# cerebro5_8_doubleboost_singlebattery.net
KiCad netlist of a schematic drawn in EAGLE
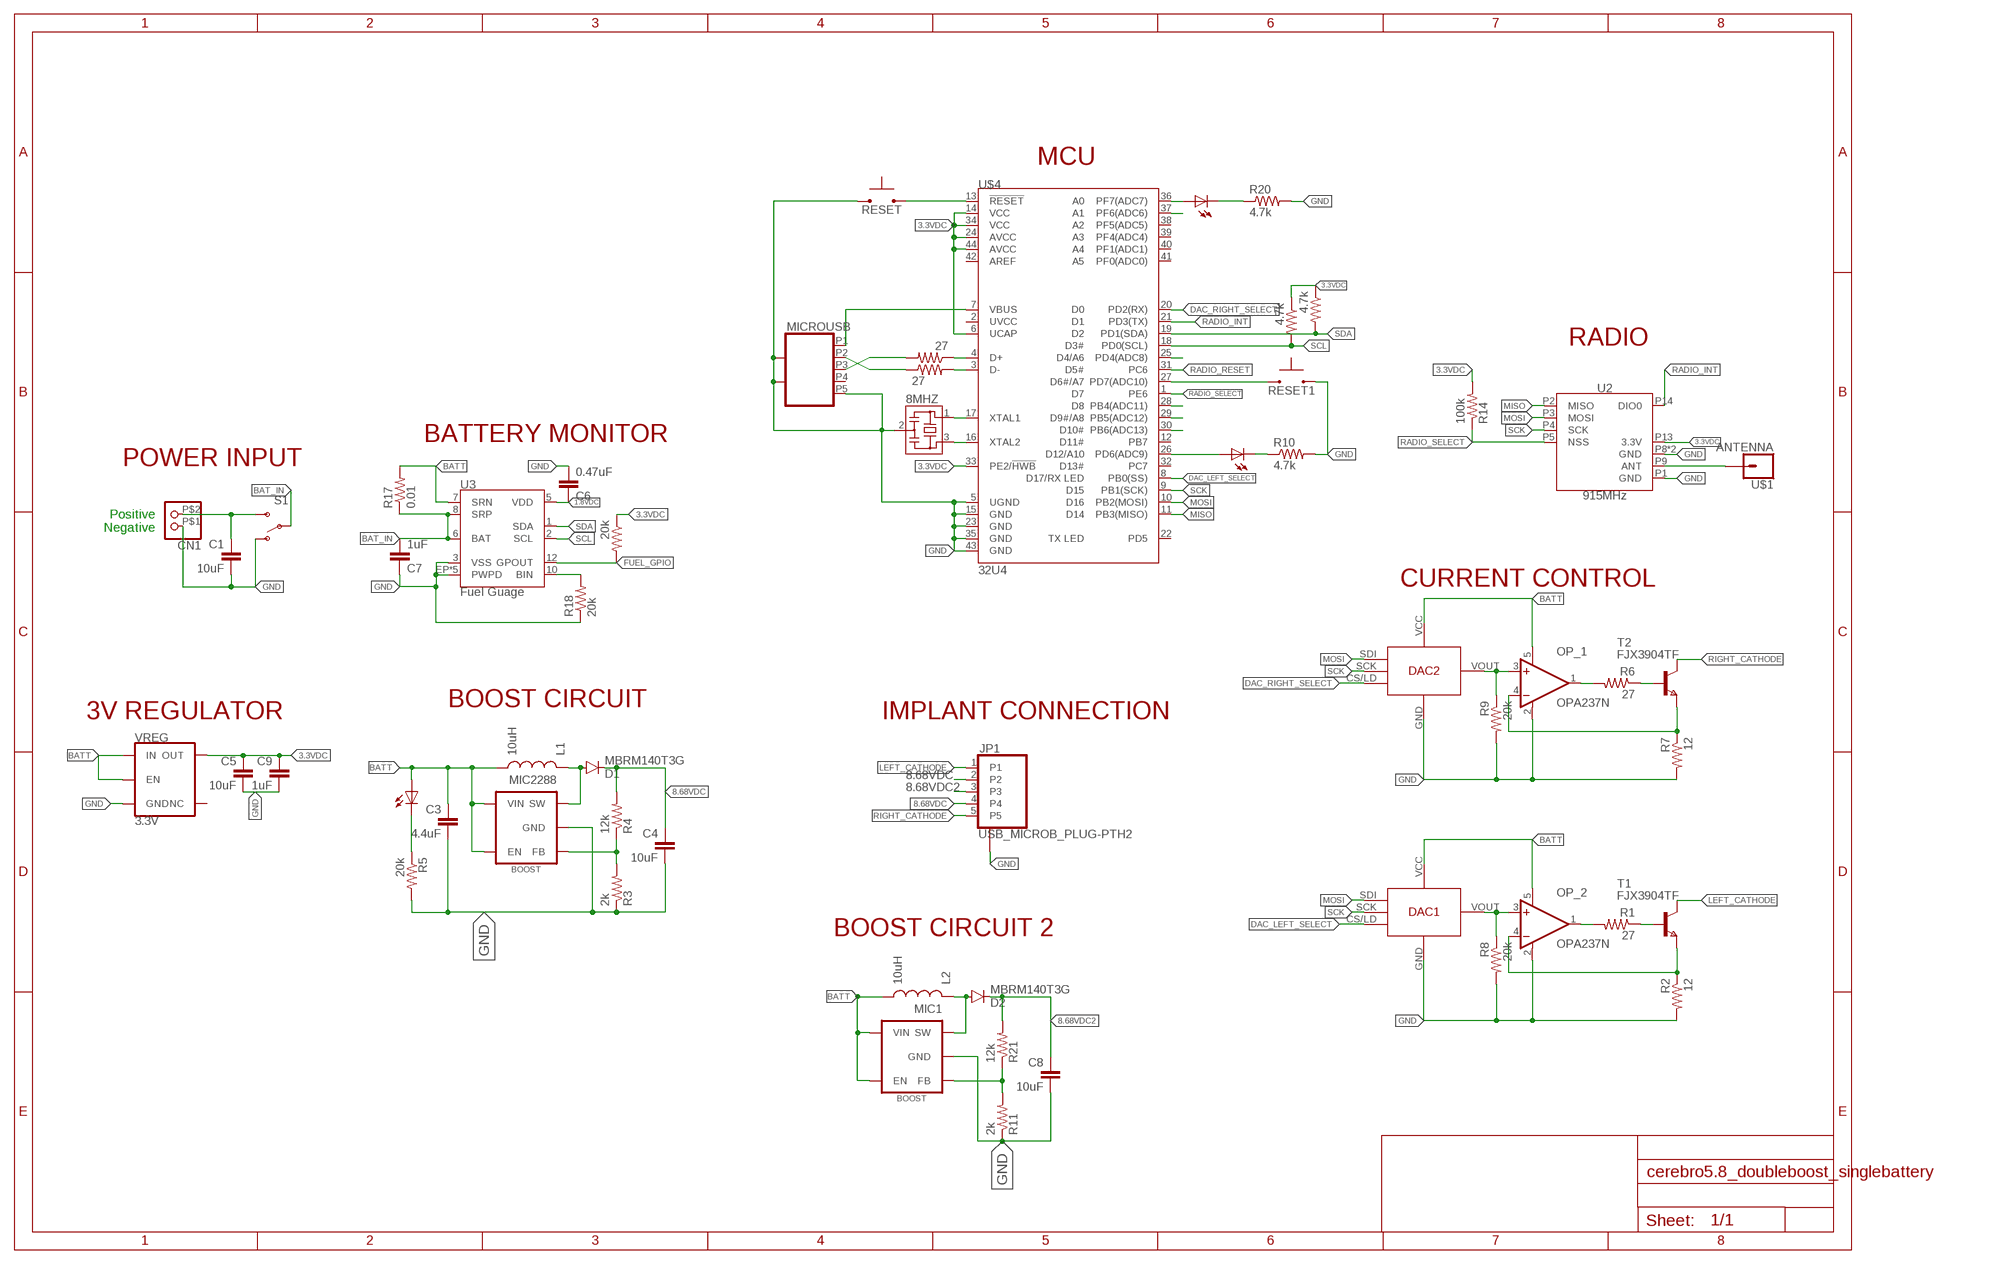
[diagram p0: schematic, sheet 1]

(export (version "E")
  (design (tool "Eeschema 10.0.6"))
  (components
    (comp (ref "8MHZ")
      (value "RESONATOR_CSTCE_V")
      (footprint "eagle-import:CSTCE_V")
      (libsource (lib "eagle-import") (part "RESONATOR_CSTCE_V"))
    )
    (comp (ref "C1")
      (value "10uF")
      (footprint "eagle-import:0805")
      (libsource (lib "eagle-import") (part "10UF-0805-10V-10%"))
    )
    (comp (ref "C3")
      (value "4.4uF")
      (footprint "eagle-import:0805")
      (libsource (lib "eagle-import") (part "2.2UF-0805-25V-(+80/-20%)"))
    )
    (comp (ref "C4")
      (value "10uF")
      (footprint "eagle-import:0805")
      (libsource (lib "eagle-import") (part "10UF-0805-10V-10%"))
    )
    (comp (ref "C5")
      (value "10uF")
      (footprint "eagle-import:0805")
      (libsource (lib "eagle-import") (part "10UF-0805-10V-10%"))
    )
    (comp (ref "C6")
      (value "0.47uF")
      (footprint "eagle-import:0805")
      (libsource (lib "eagle-import") (part "10UF-0805-10V-10%"))
    )
    (comp (ref "C7")
      (value "1uF")
      (footprint "eagle-import:0805")
      (libsource (lib "eagle-import") (part "10UF-0805-10V-10%"))
    )
    (comp (ref "C8")
      (value "10uF")
      (footprint "eagle-import:0805")
      (libsource (lib "eagle-import") (part "10UF-0805-10V-10%"))
    )
    (comp (ref "C9")
      (value "1uF")
      (footprint "eagle-import:0805")
      (libsource (lib "eagle-import") (part "10UF-0805-10V-10%"))
    )
    (comp (ref "CN1")
      (value "JST_2PINMICRO")
      (footprint "eagle-import:MICRO_LOCK_2PIN")
      (libsource (lib "eagle-import") (part "JST_2PINMICRO"))
    )
    (comp (ref "D1")
      (value "MBRM140T3G")
      (footprint "eagle-import:POWERMITE")
      (libsource (lib "eagle-import") (part "DIODEPOWERMITE"))
    )
    (comp (ref "D2")
      (value "MBRM140T3G")
      (footprint "eagle-import:POWERMITE")
      (libsource (lib "eagle-import") (part "DIODEPOWERMITE"))
    )
    (comp (ref "DAC1")
      (value "DAC")
      (footprint "eagle-import:SC-70")
      (libsource (lib "eagle-import") (part "DAC_LTC2630"))
    )
    (comp (ref "DAC2")
      (value "DAC")
      (footprint "eagle-import:SC-70")
      (libsource (lib "eagle-import") (part "DAC_LTC2630"))
    )
    (comp (ref "INDICATOR_LED")
      (value "RED")
      (footprint "eagle-import:CHIP-LED0603")
      (libsource (lib "eagle-import") (part "LEDCHIP-LED0603"))
    )
    (comp (ref "INDICATOR_LED1")
      (value "YLW")
      (footprint "eagle-import:CHIP-LED0603")
      (libsource (lib "eagle-import") (part "LEDCHIP-LED0603"))
    )
    (comp (ref "INDICATOR_LED2")
      (value "GRN")
      (footprint "eagle-import:CHIP-LED0603")
      (libsource (lib "eagle-import") (part "LEDCHIP-LED0603"))
    )
    (comp (ref "JP1")
      (value "USB_MICROB_PLUG-PTH2")
      (footprint "eagle-import:MICRO-B-TH")
      (libsource (lib "eagle-import") (part "USB_MICROB_PLUG-PTH2"))
    )
    (comp (ref "L1")
      (value "10uH")
      (footprint "eagle-import:1812")
      (libsource (lib "eagle-import") (part "INDUCTORLQH4"))
    )
    (comp (ref "L2")
      (value "10uH")
      (footprint "eagle-import:1812")
      (libsource (lib "eagle-import") (part "INDUCTORLQH4"))
    )
    (comp (ref "MIC1")
      (value "BOOST")
      (footprint "eagle-import:SOT23-5")
      (libsource (lib "eagle-import") (part "BOOST_CONVERTER"))
    )
    (comp (ref "MIC2288")
      (value "BOOST")
      (footprint "eagle-import:SOT23-5")
      (libsource (lib "eagle-import") (part "BOOST_CONVERTER"))
    )
    (comp (ref "MICROUSB")
      (value "USB_MICRO_SOCKET_HORZ_REINFORCED")
      (footprint "eagle-import:USB_HORZ_REINFORCED_MICRO")
      (libsource (lib "eagle-import") (part "USB_MICRO_SOCKET_HORZ_REINFORCED"))
    )
    (comp (ref "OP_1")
      (value "OPA237N")
      (footprint "eagle-import:SOT23-5")
      (fields (field (name "MF") "TEXAS INSTRUMENTS") (field (name "MPN") "OPA237NA/250"))
      (libsource (lib "eagle-import") (part "OPA237N"))
    )
    (comp (ref "OP_2")
      (value "OPA237N")
      (footprint "eagle-import:SOT23-5")
      (fields (field (name "MF") "TEXAS INSTRUMENTS") (field (name "MPN") "OPA237NA/250"))
      (libsource (lib "eagle-import") (part "OPA237N"))
    )
    (comp (ref "R1")
      (value "27")
      (footprint "eagle-import:0603-RES")
      (libsource (lib "eagle-import") (part "RESISTOR0603-RES"))
    )
    (comp (ref "R2")
      (value "12")
      (footprint "eagle-import:0603-RES")
      (libsource (lib "eagle-import") (part "RESISTOR0603-RES"))
    )
    (comp (ref "R3")
      (value "2k")
      (footprint "eagle-import:0603-RES")
      (libsource (lib "eagle-import") (part "RESISTOR0603-RES"))
    )
    (comp (ref "R4")
      (value "12k")
      (footprint "eagle-import:0805")
      (libsource (lib "eagle-import") (part "RESISTOR0805-RES"))
    )
    (comp (ref "R5")
      (value "20k")
      (footprint "eagle-import:0603-RES")
      (libsource (lib "eagle-import") (part "RESISTOR0603-RES"))
    )
    (comp (ref "R6")
      (value "27")
      (footprint "eagle-import:0603-RES")
      (libsource (lib "eagle-import") (part "RESISTOR0603-RES"))
    )
    (comp (ref "R7")
      (value "12")
      (footprint "eagle-import:0603-RES")
      (libsource (lib "eagle-import") (part "RESISTOR0603-RES"))
    )
    (comp (ref "R8")
      (value "20k")
      (footprint "eagle-import:0603-RES")
      (libsource (lib "eagle-import") (part "RESISTOR0603-RES"))
    )
    (comp (ref "R9")
      (value "20k")
      (footprint "eagle-import:0603-RES")
      (libsource (lib "eagle-import") (part "RESISTOR0603-RES"))
    )
    (comp (ref "R10")
      (value "4.7k")
      (footprint "eagle-import:0603-RES")
      (libsource (lib "eagle-import") (part "RESISTOR0603-RES"))
    )
    (comp (ref "R11")
      (value "2k")
      (footprint "eagle-import:0603-RES")
      (libsource (lib "eagle-import") (part "RESISTOR0603-RES"))
    )
    (comp (ref "R12")
      (value "27")
      (footprint "eagle-import:0603-RES")
      (libsource (lib "eagle-import") (part "RESISTOR0603-RES"))
    )
    (comp (ref "R13")
      (value "27")
      (footprint "eagle-import:0603-RES")
      (libsource (lib "eagle-import") (part "RESISTOR0603-RES"))
    )
    (comp (ref "R14")
      (value "100k")
      (footprint "eagle-import:0603-RES")
      (libsource (lib "eagle-import") (part "RESISTOR0603-RES"))
    )
    (comp (ref "R15")
      (value "4.7k")
      (footprint "eagle-import:0603-RES")
      (libsource (lib "eagle-import") (part "RESISTOR0603-RES"))
    )
    (comp (ref "R16")
      (value "4.7k")
      (footprint "eagle-import:0603-RES")
      (libsource (lib "eagle-import") (part "RESISTOR0603-RES"))
    )
    (comp (ref "R17")
      (value "0.01")
      (footprint "eagle-import:1206")
      (libsource (lib "eagle-import") (part "RESISTOR1206"))
    )
    (comp (ref "R18")
      (value "20k")
      (footprint "eagle-import:0603-RES")
      (libsource (lib "eagle-import") (part "RESISTOR0603-RES"))
    )
    (comp (ref "R19")
      (value "20k")
      (footprint "eagle-import:0603-RES")
      (libsource (lib "eagle-import") (part "RESISTOR0603-RES"))
    )
    (comp (ref "R20")
      (value "4.7k")
      (footprint "eagle-import:0603-RES")
      (libsource (lib "eagle-import") (part "RESISTOR0603-RES"))
    )
    (comp (ref "R21")
      (value "12k")
      (footprint "eagle-import:0805")
      (libsource (lib "eagle-import") (part "RESISTOR0805-RES"))
    )
    (comp (ref "RESET")
      (value "SWITCH-MOMENTARY-NO")
      (footprint "eagle-import:SWITCH_MOMENTARY_XS")
      (libsource (lib "eagle-import") (part "SWITCH-MOMENTARY-NO"))
    )
    (comp (ref "RESET1")
      (value "SWITCH-MOMENTARY-NO")
      (footprint "eagle-import:SWITCH_MOMENTARY_XS")
      (libsource (lib "eagle-import") (part "SWITCH-MOMENTARY-NO"))
    )
    (comp (ref "S1")
      (value "SWITCH-SPDTREINFORCED_SMD")
      (footprint "eagle-import:SWITCH-SPDT-SMD-REINFORCED")
      (libsource (lib "eagle-import") (part "SWITCH-SPDTREINFORCED_SMD"))
    )
    (comp (ref "T1")
      (value "FJX3904TF")
      (footprint "eagle-import:SOT323")
      (fields (field (name "MPN") "DSS4160U-7"))
      (libsource (lib "eagle-import") (part "NPNSOT323"))
    )
    (comp (ref "T2")
      (value "FJX3904TF")
      (footprint "eagle-import:SOT323")
      (fields (field (name "MPN") "DSS4160U-7"))
      (libsource (lib "eagle-import") (part "NPNSOT323"))
    )
    (comp (ref "U$1")
      (value "ANTENNA")
      (footprint "eagle-import:1X01")
      (libsource (lib "eagle-import") (part "ANTENNA"))
    )
    (comp (ref "U$4")
      (value "32U4")
      (footprint "eagle-import:QFN-44-NOPAD")
      (libsource (lib "eagle-import") (part "ATMEGA32U4QFN2"))
    )
    (comp (ref "U2")
      (value "915MHz")
      (footprint "eagle-import:RFM69HCW-XXXS2")
      (libsource (lib "eagle-import") (part "RFM69HCW-915"))
    )
    (comp (ref "U3")
      (value "Fuel Guage")
      (footprint "eagle-import:PDSO-N12")
      (libsource (lib "eagle-import") (part "BQ27441-G1"))
    )
    (comp (ref "VREG")
      (value "3.3V")
      (footprint "eagle-import:SOT23-5")
      (libsource (lib "eagle-import") (part "V_REG_AP2112K-3.3V"))
    )
  )
  (nets
    (net (code "1") (name "1.8VDC") (class "Default")
      (node (ref "C6") (pin "1") (pinfunction "1_1") (pintype "passive"))
      (node (ref "U3") (pin "5") (pinfunction "VDD_5") (pintype "bidirectional"))
    )
    (net (code "2") (name "3.3VDC") (class "Default")
      (node (ref "C5") (pin "1") (pinfunction "1_1") (pintype "passive"))
      (node (ref "C9") (pin "1") (pinfunction "1_1") (pintype "passive"))
      (node (ref "R14") (pin "2") (pinfunction "2_2") (pintype "passive"))
      (node (ref "R15") (pin "1") (pinfunction "1_1") (pintype "passive"))
      (node (ref "R16") (pin "1") (pinfunction "1_1") (pintype "passive"))
      (node (ref "R19") (pin "1") (pinfunction "1_1") (pintype "passive"))
      (node (ref "U$4") (pin "14") (pinfunction "VCC_14") (pintype "bidirectional"))
      (node (ref "U$4") (pin "24") (pinfunction "AVCC_24") (pintype "bidirectional"))
      (node (ref "U$4") (pin "33") (pinfunction "PE2/~{HWB}_33") (pintype "bidirectional"))
      (node (ref "U$4") (pin "34") (pinfunction "VCC_34") (pintype "bidirectional"))
      (node (ref "U$4") (pin "44") (pinfunction "AVCC_44") (pintype "bidirectional"))
      (node (ref "U$4") (pin "6") (pinfunction "UCAP_6") (pintype "bidirectional"))
      (node (ref "U2") (pin "P13") (pinfunction "3.3V_P13") (pintype "power_in"))
      (node (ref "VREG") (pin "5") (pinfunction "OUT_5") (pintype "passive"))
    )
    (net (code "3") (name "8.68VDC") (class "Default")
      (node (ref "C4") (pin "1") (pinfunction "1_1") (pintype "passive"))
      (node (ref "D1") (pin "CATHODE") (pinfunction "C_CATHODE") (pintype "passive"))
      (node (ref "JP1") (pin "2") (pinfunction "P2_2") (pintype "bidirectional"))
      (node (ref "JP1") (pin "4") (pinfunction "P4_4") (pintype "bidirectional"))
      (node (ref "R4") (pin "2") (pinfunction "2_2") (pintype "passive"))
    )
    (net (code "4") (name "8.68VDC2") (class "Default")
      (node (ref "C8") (pin "1") (pinfunction "1_1") (pintype "passive"))
      (node (ref "D2") (pin "CATHODE") (pinfunction "C_CATHODE") (pintype "passive"))
      (node (ref "JP1") (pin "3") (pinfunction "P3_3") (pintype "bidirectional"))
      (node (ref "R21") (pin "2") (pinfunction "2_2") (pintype "passive"))
    )
    (net (code "5") (name "BATT") (class "Default")
      (node (ref "C3") (pin "1") (pinfunction "1_1") (pintype "passive"))
      (node (ref "DAC1") (pin "VCC") (pinfunction "VIN_VCC") (pintype "bidirectional"))
      (node (ref "DAC2") (pin "VCC") (pinfunction "VIN_VCC") (pintype "bidirectional"))
      (node (ref "INDICATOR_LED") (pin "A") (pinfunction "A_A") (pintype "passive"))
      (node (ref "L1") (pin "P$2") (pinfunction "2_P$2") (pintype "passive"))
      (node (ref "L1") (pin "P$4") (pinfunction "2_P$4") (pintype "passive"))
      (node (ref "L2") (pin "P$2") (pinfunction "2_P$2") (pintype "passive"))
      (node (ref "L2") (pin "P$4") (pinfunction "2_P$4") (pintype "passive"))
      (node (ref "MIC1") (pin "4") (pinfunction "EN_4") (pintype "input"))
      (node (ref "MIC1") (pin "5") (pinfunction "VIN_5") (pintype "passive"))
      (node (ref "MIC2288") (pin "4") (pinfunction "EN_4") (pintype "input"))
      (node (ref "MIC2288") (pin "5") (pinfunction "VIN_5") (pintype "passive"))
      (node (ref "OP_1") (pin "5") (pinfunction "V+_5") (pintype "power_in"))
      (node (ref "OP_2") (pin "5") (pinfunction "V+_5") (pintype "power_in"))
      (node (ref "R17") (pin "2") (pinfunction "2_2") (pintype "passive"))
      (node (ref "U3") (pin "7") (pinfunction "SRN_7") (pintype "bidirectional"))
      (node (ref "VREG") (pin "1") (pinfunction "IN_1") (pintype "input"))
      (node (ref "VREG") (pin "3") (pinfunction "EN_3") (pintype "input"))
    )
    (net (code "6") (name "BAT_IN") (class "Default")
      (node (ref "C7") (pin "2") (pinfunction "2_2") (pintype "passive"))
      (node (ref "R17") (pin "1") (pinfunction "1_1") (pintype "passive"))
      (node (ref "S1") (pin "2") (pinfunction "P_2") (pintype "passive"))
      (node (ref "U3") (pin "6") (pinfunction "BAT_6") (pintype "bidirectional"))
      (node (ref "U3") (pin "8") (pinfunction "SRP_8") (pintype "bidirectional"))
    )
    (net (code "7") (name "DAC_LEFT_SELECT") (class "Default")
      (node (ref "DAC1") (pin "CS/LD") (pinfunction "CS/LD_CS/LD") (pintype "bidirectional"))
      (node (ref "U$4") (pin "8") (pinfunction "PB0(SS)_8") (pintype "bidirectional"))
    )
    (net (code "8") (name "DAC_RIGHT_SELECT") (class "Default")
      (node (ref "DAC2") (pin "CS/LD") (pinfunction "CS/LD_CS/LD") (pintype "bidirectional"))
      (node (ref "U$4") (pin "20") (pinfunction "PD2(RX)_20") (pintype "bidirectional"))
    )
    (net (code "9") (name "FUEL_GPIO") (class "Default")
      (node (ref "R19") (pin "2") (pinfunction "2_2") (pintype "passive"))
      (node (ref "U3") (pin "12") (pinfunction "GPOUT_12") (pintype "bidirectional"))
    )
    (net (code "10") (name "GND") (class "Default")
      (node (ref "8MHZ") (pin "2") (pinfunction "2_2") (pintype "passive"))
      (node (ref "C1") (pin "2") (pinfunction "2_2") (pintype "passive"))
      (node (ref "C3") (pin "2") (pinfunction "2_2") (pintype "passive"))
      (node (ref "C4") (pin "2") (pinfunction "2_2") (pintype "passive"))
      (node (ref "C5") (pin "2") (pinfunction "2_2") (pintype "passive"))
      (node (ref "C6") (pin "2") (pinfunction "2_2") (pintype "passive"))
      (node (ref "C7") (pin "1") (pinfunction "1_1") (pintype "passive"))
      (node (ref "C8") (pin "2") (pinfunction "2_2") (pintype "passive"))
      (node (ref "C9") (pin "2") (pinfunction "2_2") (pintype "passive"))
      (node (ref "CN1") (pin "P$1") (pinfunction "1_P$1") (pintype "passive"))
      (node (ref "DAC1") (pin "GND") (pinfunction "GND_GND") (pintype "bidirectional"))
      (node (ref "DAC2") (pin "GND") (pinfunction "GND_GND") (pintype "bidirectional"))
      (node (ref "JP1") (pin "P$1") (pinfunction "GND_PINS_P$1") (pintype "bidirectional"))
      (node (ref "JP1") (pin "P$2") (pinfunction "GND_PINS_P$2") (pintype "bidirectional"))
      (node (ref "MIC1") (pin "2") (pinfunction "GND_2") (pintype "input"))
      (node (ref "MIC2288") (pin "2") (pinfunction "GND_2") (pintype "input"))
      (node (ref "MICROUSB") (pin "G1") (pinfunction "P$1_G1") (pintype "bidirectional"))
      (node (ref "MICROUSB") (pin "G2") (pinfunction "P$1_G2") (pintype "bidirectional"))
      (node (ref "MICROUSB") (pin "P$1") (pinfunction "P$2_P$1") (pintype "bidirectional"))
      (node (ref "MICROUSB") (pin "P$2") (pinfunction "P$2_P$2") (pintype "bidirectional"))
      (node (ref "MICROUSB") (pin "P5") (pinfunction "P5_P5") (pintype "bidirectional"))
      (node (ref "OP_1") (pin "2") (pinfunction "V-_2") (pintype "power_in"))
      (node (ref "OP_2") (pin "2") (pinfunction "V-_2") (pintype "power_in"))
      (node (ref "R10") (pin "2") (pinfunction "2_2") (pintype "passive"))
      (node (ref "R11") (pin "1") (pinfunction "1_1") (pintype "passive"))
      (node (ref "R18") (pin "1") (pinfunction "1_1") (pintype "passive"))
      (node (ref "R2") (pin "2") (pinfunction "2_2") (pintype "passive"))
      (node (ref "R20") (pin "2") (pinfunction "2_2") (pintype "passive"))
      (node (ref "R3") (pin "1") (pinfunction "1_1") (pintype "passive"))
      (node (ref "R5") (pin "2") (pinfunction "2_2") (pintype "passive"))
      (node (ref "R7") (pin "2") (pinfunction "2_2") (pintype "passive"))
      (node (ref "R8") (pin "2") (pinfunction "2_2") (pintype "passive"))
      (node (ref "R9") (pin "2") (pinfunction "2_2") (pintype "passive"))
      (node (ref "RESET") (pin "P$1") (pinfunction "1_P$1") (pintype "bidirectional"))
      (node (ref "RESET1") (pin "P$2") (pinfunction "2_P$2") (pintype "bidirectional"))
      (node (ref "S1") (pin "1") (pinfunction "O_1") (pintype "passive"))
      (node (ref "U$4") (pin "15") (pinfunction "GND_15") (pintype "bidirectional"))
      (node (ref "U$4") (pin "23") (pinfunction "GND_23") (pintype "bidirectional"))
      (node (ref "U$4") (pin "35") (pinfunction "GND_35") (pintype "bidirectional"))
      (node (ref "U$4") (pin "43") (pinfunction "GND_43") (pintype "bidirectional"))
      (node (ref "U$4") (pin "5") (pinfunction "UGND_5") (pintype "bidirectional"))
      (node (ref "U2") (pin "P1") (pinfunction "GND_P1") (pintype "power_in"))
      (node (ref "U2") (pin "P10") (pinfunction "GND_P10") (pintype "power_in"))
      (node (ref "U2") (pin "P8") (pinfunction "GND_P8") (pintype "power_in"))
      (node (ref "U3") (pin "3") (pinfunction "VSS_3") (pintype "bidirectional"))
      (node (ref "U3") (pin "EP") (pinfunction "PWPD_EP") (pintype "bidirectional"))
      (node (ref "U3") (pin "EP1") (pinfunction "PWPD_EP1") (pintype "bidirectional"))
      (node (ref "U3") (pin "EP2") (pinfunction "PWPD_EP2") (pintype "bidirectional"))
      (node (ref "U3") (pin "EP3") (pinfunction "PWPD_EP3") (pintype "bidirectional"))
      (node (ref "U3") (pin "EP4") (pinfunction "PWPD_EP4") (pintype "bidirectional"))
      (node (ref "VREG") (pin "2") (pinfunction "GND_2") (pintype "input"))
    )
    (net (code "11") (name "LEFT_CATHODE") (class "Default")
      (node (ref "JP1") (pin "1") (pinfunction "P1_1") (pintype "bidirectional"))
      (node (ref "T1") (pin "1") (pinfunction "C_1") (pintype "passive"))
    )
    (net (code "12") (name "MISO") (class "Default")
      (node (ref "U$4") (pin "11") (pinfunction "PB3(MISO)_11") (pintype "bidirectional"))
      (node (ref "U2") (pin "P2") (pinfunction "MISO_P2") (pintype "bidirectional"))
    )
    (net (code "13") (name "MOSI") (class "Default")
      (node (ref "DAC1") (pin "SDI") (pinfunction "SDI_SDI") (pintype "bidirectional"))
      (node (ref "DAC2") (pin "SDI") (pinfunction "SDI_SDI") (pintype "bidirectional"))
      (node (ref "U$4") (pin "10") (pinfunction "PB2(MOSI)_10") (pintype "bidirectional"))
      (node (ref "U2") (pin "P3") (pinfunction "MOSI_P3") (pintype "input"))
    )
    (net (code "14") (name "Net-(CN1-2)") (class "Default")
      (node (ref "C1") (pin "1") (pinfunction "1_1") (pintype "passive"))
      (node (ref "CN1") (pin "P$2") (pinfunction "2_P$2") (pintype "passive"))
      (node (ref "S1") (pin "3") (pinfunction "S_3") (pintype "passive"))
    )
    (net (code "15") (name "Net-(D1-A)") (class "Default")
      (node (ref "D1") (pin "ANODE") (pinfunction "A_ANODE") (pintype "passive"))
      (node (ref "L1") (pin "P$1") (pinfunction "1_P$1") (pintype "passive"))
      (node (ref "L1") (pin "P$3") (pinfunction "1_P$3") (pintype "passive"))
      (node (ref "MIC2288") (pin "1") (pinfunction "SW_1") (pintype "input"))
    )
    (net (code "16") (name "Net-(D2-A)") (class "Default")
      (node (ref "D2") (pin "ANODE") (pinfunction "A_ANODE") (pintype "passive"))
      (node (ref "L2") (pin "P$1") (pinfunction "1_P$1") (pintype "passive"))
      (node (ref "L2") (pin "P$3") (pinfunction "1_P$3") (pintype "passive"))
      (node (ref "MIC1") (pin "1") (pinfunction "SW_1") (pintype "input"))
    )
    (net (code "17") (name "Net-(INDICATOR_LED-PadC)") (class "Default")
      (node (ref "INDICATOR_LED") (pin "C") (pinfunction "C_C") (pintype "passive"))
      (node (ref "R5") (pin "1") (pinfunction "1_1") (pintype "passive"))
    )
    (net (code "18") (name "Net-(INDICATOR_LED1-PadC)") (class "Default")
      (node (ref "INDICATOR_LED1") (pin "C") (pinfunction "C_C") (pintype "passive"))
      (node (ref "R20") (pin "1") (pinfunction "1_1") (pintype "passive"))
    )
    (net (code "19") (name "Net-(INDICATOR_LED2-PadC)") (class "Default")
      (node (ref "INDICATOR_LED2") (pin "C") (pinfunction "C_C") (pintype "passive"))
      (node (ref "R10") (pin "1") (pinfunction "1_1") (pintype "passive"))
    )
    (net (code "20") (name "Net-(MIC1-FB)") (class "Default")
      (node (ref "MIC1") (pin "3") (pinfunction "FB_3") (pintype "input"))
      (node (ref "R11") (pin "2") (pinfunction "2_2") (pintype "passive"))
      (node (ref "R21") (pin "1") (pinfunction "1_1") (pintype "passive"))
    )
    (net (code "21") (name "Net-(MIC2288-FB)") (class "Default")
      (node (ref "MIC2288") (pin "3") (pinfunction "FB_3") (pintype "input"))
      (node (ref "R3") (pin "2") (pinfunction "2_2") (pintype "passive"))
      (node (ref "R4") (pin "1") (pinfunction "1_1") (pintype "passive"))
    )
    (net (code "22") (name "Net-(MICROUSB-PadP2)") (class "Default")
      (node (ref "MICROUSB") (pin "P2") (pinfunction "P2_P2") (pintype "bidirectional"))
      (node (ref "R13") (pin "1") (pinfunction "1_1") (pintype "passive"))
    )
    (net (code "23") (name "Net-(MICROUSB-PadP3)") (class "Default")
      (node (ref "MICROUSB") (pin "P3") (pinfunction "P3_P3") (pintype "bidirectional"))
      (node (ref "R12") (pin "2") (pinfunction "2_2") (pintype "passive"))
    )
    (net (code "24") (name "Net-(OP_1-+IN)") (class "Default")
      (node (ref "DAC2") (pin "VOUT") (pinfunction "VOUT_VOUT") (pintype "bidirectional"))
      (node (ref "OP_1") (pin "3") (pinfunction "+IN_3") (pintype "input"))
      (node (ref "R9") (pin "1") (pinfunction "1_1") (pintype "passive"))
    )
    (net (code "25") (name "Net-(OP_1--IN)") (class "Default")
      (node (ref "OP_1") (pin "4") (pinfunction "-IN_4") (pintype "input"))
      (node (ref "R7") (pin "1") (pinfunction "1_1") (pintype "passive"))
      (node (ref "T2") (pin "3") (pinfunction "E_3") (pintype "passive"))
    )
    (net (code "26") (name "Net-(OP_1-OUT)") (class "Default")
      (node (ref "OP_1") (pin "1") (pinfunction "OUT_1") (pintype "output"))
      (node (ref "R6") (pin "2") (pinfunction "2_2") (pintype "passive"))
    )
    (net (code "27") (name "Net-(OP_2-+IN)") (class "Default")
      (node (ref "DAC1") (pin "VOUT") (pinfunction "VOUT_VOUT") (pintype "bidirectional"))
      (node (ref "OP_2") (pin "3") (pinfunction "+IN_3") (pintype "input"))
      (node (ref "R8") (pin "1") (pinfunction "1_1") (pintype "passive"))
    )
    (net (code "28") (name "Net-(OP_2--IN)") (class "Default")
      (node (ref "OP_2") (pin "4") (pinfunction "-IN_4") (pintype "input"))
      (node (ref "R2") (pin "1") (pinfunction "1_1") (pintype "passive"))
      (node (ref "T1") (pin "3") (pinfunction "E_3") (pintype "passive"))
    )
    (net (code "29") (name "Net-(OP_2-OUT)") (class "Default")
      (node (ref "OP_2") (pin "1") (pinfunction "OUT_1") (pintype "output"))
      (node (ref "R1") (pin "2") (pinfunction "2_2") (pintype "passive"))
    )
    (net (code "30") (name "Net-(RESET-2)") (class "Default")
      (node (ref "RESET") (pin "P$2") (pinfunction "2_P$2") (pintype "bidirectional"))
      (node (ref "U$4") (pin "13") (pinfunction "~{RESET}_13") (pintype "bidirectional"))
    )
    (net (code "31") (name "Net-(RESET1-1)") (class "Default")
      (node (ref "RESET1") (pin "P$1") (pinfunction "1_P$1") (pintype "bidirectional"))
      (node (ref "U$4") (pin "27") (pinfunction "PD7(ADC10)_27") (pintype "bidirectional"))
    )
    (net (code "32") (name "Net-(T1-B)") (class "Default")
      (node (ref "R1") (pin "1") (pinfunction "1_1") (pintype "passive"))
      (node (ref "T1") (pin "2") (pinfunction "B_2") (pintype "passive"))
    )
    (net (code "33") (name "Net-(T2-B)") (class "Default")
      (node (ref "R6") (pin "1") (pinfunction "1_1") (pintype "passive"))
      (node (ref "T2") (pin "2") (pinfunction "B_2") (pintype "passive"))
    )
    (net (code "34") (name "Net-(U$4-D+)") (class "Default")
      (node (ref "R12") (pin "1") (pinfunction "1_1") (pintype "passive"))
      (node (ref "U$4") (pin "4") (pinfunction "D+_4") (pintype "bidirectional"))
    )
    (net (code "35") (name "Net-(U$4-D-)") (class "Default")
      (node (ref "R13") (pin "2") (pinfunction "2_2") (pintype "passive"))
      (node (ref "U$4") (pin "3") (pinfunction "D-_3") (pintype "bidirectional"))
    )
    (net (code "36") (name "Net-(U$4-PD6(ADC9))") (class "Default")
      (node (ref "INDICATOR_LED2") (pin "A") (pinfunction "A_A") (pintype "passive"))
      (node (ref "U$4") (pin "26") (pinfunction "PD6(ADC9)_26") (pintype "bidirectional"))
    )
    (net (code "37") (name "Net-(U$4-PF7(ADC7))") (class "Default")
      (node (ref "INDICATOR_LED1") (pin "A") (pinfunction "A_A") (pintype "passive"))
      (node (ref "U$4") (pin "36") (pinfunction "PF7(ADC7)_36") (pintype "bidirectional"))
    )
    (net (code "38") (name "Net-(U$4-VBUS)") (class "Default")
      (node (ref "MICROUSB") (pin "P1") (pinfunction "P1_P1") (pintype "bidirectional"))
      (node (ref "U$4") (pin "7") (pinfunction "VBUS_7") (pintype "bidirectional"))
    )
    (net (code "39") (name "Net-(U$4-XTAL1)") (class "Default")
      (node (ref "8MHZ") (pin "1") (pinfunction "1_1") (pintype "passive"))
      (node (ref "U$4") (pin "17") (pinfunction "XTAL1_17") (pintype "bidirectional"))
    )
    (net (code "40") (name "Net-(U$4-XTAL2)") (class "Default")
      (node (ref "8MHZ") (pin "3") (pinfunction "3_3") (pintype "passive"))
      (node (ref "U$4") (pin "16") (pinfunction "XTAL2_16") (pintype "bidirectional"))
    )
    (net (code "41") (name "Net-(U2-ANT)") (class "Default")
      (node (ref "U$1") (pin "1") (pinfunction "1_1") (pintype "passive"))
      (node (ref "U2") (pin "P9") (pinfunction "ANT_P9") (pintype "passive"))
    )
    (net (code "42") (name "Net-(U3-BIN)") (class "Default")
      (node (ref "R18") (pin "2") (pinfunction "2_2") (pintype "passive"))
      (node (ref "U3") (pin "10") (pinfunction "BIN_10") (pintype "bidirectional"))
    )
    (net (code "43") (name "RADIO_INT") (class "Default")
      (node (ref "U$4") (pin "21") (pinfunction "PD3(TX)_21") (pintype "bidirectional"))
      (node (ref "U2") (pin "P14") (pinfunction "DIO0_P14") (pintype "bidirectional"))
    )
    (net (code "44") (name "RADIO_RESET") (class "Default")
      (node (ref "U$4") (pin "31") (pinfunction "PC6_31") (pintype "bidirectional"))
    )
    (net (code "45") (name "RADIO_SELECT") (class "Default")
      (node (ref "R14") (pin "1") (pinfunction "1_1") (pintype "passive"))
      (node (ref "U$4") (pin "1") (pinfunction "PE6_1") (pintype "bidirectional"))
      (node (ref "U2") (pin "P5") (pinfunction "NSS_P5") (pintype "input"))
    )
    (net (code "46") (name "RIGHT_CATHODE") (class "Default")
      (node (ref "JP1") (pin "5") (pinfunction "P5_5") (pintype "bidirectional"))
      (node (ref "T2") (pin "1") (pinfunction "C_1") (pintype "passive"))
    )
    (net (code "47") (name "SCK") (class "Default")
      (node (ref "DAC1") (pin "SCK") (pinfunction "SCK_SCK") (pintype "bidirectional"))
      (node (ref "DAC2") (pin "SCK") (pinfunction "SCK_SCK") (pintype "bidirectional"))
      (node (ref "U$4") (pin "9") (pinfunction "PB1(SCK)_9") (pintype "bidirectional"))
      (node (ref "U2") (pin "P4") (pinfunction "SCK_P4") (pintype "input"))
    )
    (net (code "48") (name "SCL") (class "Default")
      (node (ref "R15") (pin "2") (pinfunction "2_2") (pintype "passive"))
      (node (ref "U$4") (pin "18") (pinfunction "PD0(SCL)_18") (pintype "bidirectional"))
      (node (ref "U3") (pin "2") (pinfunction "SCL_2") (pintype "bidirectional"))
    )
    (net (code "49") (name "SDA") (class "Default")
      (node (ref "R16") (pin "2") (pinfunction "2_2") (pintype "passive"))
      (node (ref "U$4") (pin "19") (pinfunction "PD1(SDA)_19") (pintype "bidirectional"))
      (node (ref "U3") (pin "1") (pinfunction "SDA_1") (pintype "bidirectional"))
    )
    (net (code "50") (name "unconnected-(MICROUSB-PadP4)") (class "Default")
      (node (ref "MICROUSB") (pin "P4") (pinfunction "P4_P4") (pintype "bidirectional"))
    )
    (net (code "51") (name "unconnected-(U$4-AREF-Pad42)") (class "Default")
      (node (ref "U$4") (pin "42") (pinfunction "AREF_42") (pintype "bidirectional"))
    )
    (net (code "52") (name "unconnected-(U$4-PB4(ADC11)-Pad28)") (class "Default")
      (node (ref "U$4") (pin "28") (pinfunction "PB4(ADC11)_28") (pintype "bidirectional"))
    )
    (net (code "53") (name "unconnected-(U$4-PB5(ADC12)-Pad29)") (class "Default")
      (node (ref "U$4") (pin "29") (pinfunction "PB5(ADC12)_29") (pintype "bidirectional"))
    )
    (net (code "54") (name "unconnected-(U$4-PB6(ADC13)-Pad30)") (class "Default")
      (node (ref "U$4") (pin "30") (pinfunction "PB6(ADC13)_30") (pintype "bidirectional"))
    )
    (net (code "55") (name "unconnected-(U$4-PB7-Pad12)") (class "Default")
      (node (ref "U$4") (pin "12") (pinfunction "PB7_12") (pintype "bidirectional"))
    )
    (net (code "56") (name "unconnected-(U$4-PC7-Pad32)") (class "Default")
      (node (ref "U$4") (pin "32") (pinfunction "PC7_32") (pintype "bidirectional"))
    )
    (net (code "57") (name "unconnected-(U$4-PD4(ADC8)-Pad25)") (class "Default")
      (node (ref "U$4") (pin "25") (pinfunction "PD4(ADC8)_25") (pintype "bidirectional"))
    )
    (net (code "58") (name "unconnected-(U$4-PD5-Pad22)") (class "Default")
      (node (ref "U$4") (pin "22") (pinfunction "PD5_22") (pintype "bidirectional"))
    )
    (net (code "59") (name "unconnected-(U$4-PF0(ADC0)-Pad41)") (class "Default")
      (node (ref "U$4") (pin "41") (pinfunction "PF0(ADC0)_41") (pintype "bidirectional"))
    )
    (net (code "60") (name "unconnected-(U$4-PF1(ADC1)-Pad40)") (class "Default")
      (node (ref "U$4") (pin "40") (pinfunction "PF1(ADC1)_40") (pintype "bidirectional"))
    )
    (net (code "61") (name "unconnected-(U$4-PF4(ADC4)-Pad39)") (class "Default")
      (node (ref "U$4") (pin "39") (pinfunction "PF4(ADC4)_39") (pintype "bidirectional"))
    )
    (net (code "62") (name "unconnected-(U$4-PF5(ADC5)-Pad38)") (class "Default")
      (node (ref "U$4") (pin "38") (pinfunction "PF5(ADC5)_38") (pintype "bidirectional"))
    )
    (net (code "63") (name "unconnected-(U$4-PF6(ADC6)-Pad37)") (class "Default")
      (node (ref "U$4") (pin "37") (pinfunction "PF6(ADC6)_37") (pintype "bidirectional"))
    )
    (net (code "64") (name "unconnected-(U$4-UVCC-Pad2)") (class "Default")
      (node (ref "U$4") (pin "2") (pinfunction "UVCC_2") (pintype "bidirectional"))
    )
    (net (code "65") (name "unconnected-(VREG-NC-Pad4)") (class "Default")
      (node (ref "VREG") (pin "4") (pinfunction "NC_4") (pintype "no_connect"))
    )
  )
)
